# design.net
KiCad netlist of a schematic drawn in Altium Designer
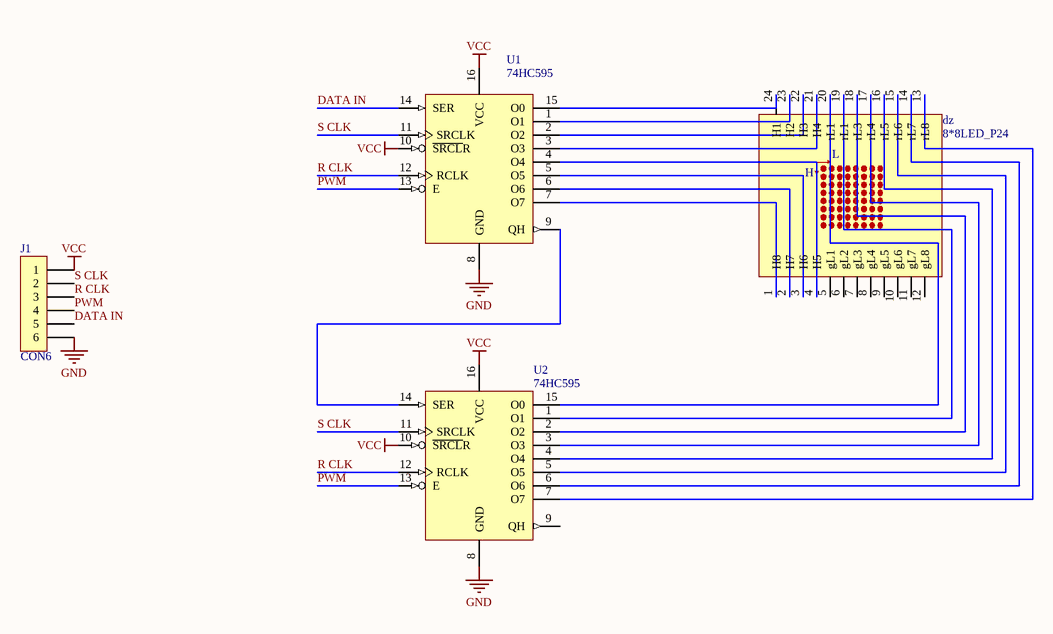
[diagram p0: 点阵.SchDoc]

(export (version "E")
  (design (tool "Eeschema 10.0.6"))
  (components
    (comp (ref "dz") (value "8*8LED_P24") (footprint "双色点阵") (libsource (lib "LED数码管") (part "8*8LED_P24")))
    (comp (ref "J1")
      (value "CON6")
      (footprint "sip-6")
      (description "Connector")
      (libsource (lib "接口") (part "CON6"))
    )
    (comp (ref "U1") (value "74HC595") (footprint "DIP-16") (libsource (lib "74xxTTL") (part "74HC595")))
    (comp (ref "U2") (value "74HC595") (footprint "DIP-16") (libsource (lib "74xxTTL") (part "74HC595")))
  )
  (nets
    (net (code "1") (name "/DATA IN") (class "Default")
      (node (ref "J1") (pin "5") (pinfunction "5_5") (pintype "passive"))
      (node (ref "U1") (pin "14") (pinfunction "SER_14") (pintype "input"))
    )
    (net (code "2") (name "/PWM") (class "Default")
      (node (ref "J1") (pin "4") (pinfunction "4_4") (pintype "passive"))
      (node (ref "U1") (pin "13") (pinfunction "E_13") (pintype "input"))
      (node (ref "U2") (pin "13") (pinfunction "E_13") (pintype "input"))
    )
    (net (code "3") (name "/R CLK") (class "Default")
      (node (ref "J1") (pin "3") (pinfunction "3_3") (pintype "passive"))
      (node (ref "U1") (pin "12") (pinfunction "RCLK_12") (pintype "input"))
      (node (ref "U2") (pin "12") (pinfunction "RCLK_12") (pintype "input"))
    )
    (net (code "4") (name "/S CLK") (class "Default")
      (node (ref "J1") (pin "2") (pinfunction "2_2") (pintype "passive"))
      (node (ref "U1") (pin "11") (pinfunction "SRCLK_11") (pintype "input"))
      (node (ref "U2") (pin "11") (pinfunction "SRCLK_11") (pintype "input"))
    )
    (net (code "5") (name "GND") (class "Default")
      (node (ref "J1") (pin "6") (pinfunction "6_6") (pintype "passive"))
      (node (ref "U1") (pin "8") (pinfunction "GND_8") (pintype "power_in"))
      (node (ref "U2") (pin "8") (pinfunction "GND_8") (pintype "power_in"))
    )
    (net (code "6") (name "Net-(U1-O0)") (class "Default")
      (node (ref "U1") (pin "15") (pinfunction "O0_15") (pintype "tri_state"))
      (node (ref "dz") (pin "24") (pinfunction "H1_24") (pintype "passive"))
    )
    (net (code "7") (name "Net-(U1-O1)") (class "Default")
      (node (ref "U1") (pin "1") (pinfunction "O1_1") (pintype "tri_state"))
      (node (ref "dz") (pin "23") (pinfunction "H2_23") (pintype "passive"))
    )
    (net (code "8") (name "Net-(U1-O2)") (class "Default")
      (node (ref "U1") (pin "2") (pinfunction "O2_2") (pintype "tri_state"))
      (node (ref "dz") (pin "22") (pinfunction "H3_22") (pintype "passive"))
    )
    (net (code "9") (name "Net-(U1-O3)") (class "Default")
      (node (ref "U1") (pin "3") (pinfunction "O3_3") (pintype "tri_state"))
      (node (ref "dz") (pin "21") (pinfunction "H4_21") (pintype "passive"))
    )
    (net (code "10") (name "Net-(U1-O4)") (class "Default")
      (node (ref "U1") (pin "4") (pinfunction "O4_4") (pintype "tri_state"))
      (node (ref "dz") (pin "4") (pinfunction "H5_4") (pintype "passive"))
    )
    (net (code "11") (name "Net-(U1-O5)") (class "Default")
      (node (ref "U1") (pin "5") (pinfunction "O5_5") (pintype "tri_state"))
      (node (ref "dz") (pin "3") (pinfunction "H6_3") (pintype "passive"))
    )
    (net (code "12") (name "Net-(U1-O6)") (class "Default")
      (node (ref "U1") (pin "6") (pinfunction "O6_6") (pintype "tri_state"))
      (node (ref "dz") (pin "2") (pinfunction "H7_2") (pintype "passive"))
    )
    (net (code "13") (name "Net-(U1-O7)") (class "Default")
      (node (ref "U1") (pin "7") (pinfunction "O7_7") (pintype "tri_state"))
      (node (ref "dz") (pin "1") (pinfunction "H8_1") (pintype "passive"))
    )
    (net (code "14") (name "Net-(U1-QH)") (class "Default")
      (node (ref "U1") (pin "9") (pinfunction "QH_9") (pintype "output"))
      (node (ref "U2") (pin "14") (pinfunction "SER_14") (pintype "input"))
    )
    (net (code "15") (name "Net-(U2-O0)") (class "Default")
      (node (ref "U2") (pin "15") (pinfunction "O0_15") (pintype "tri_state"))
      (node (ref "dz") (pin "20") (pinfunction "rL1_20") (pintype "passive"))
    )
    (net (code "16") (name "Net-(U2-O1)") (class "Default")
      (node (ref "U2") (pin "1") (pinfunction "O1_1") (pintype "tri_state"))
      (node (ref "dz") (pin "19") (pinfunction "rL1_19") (pintype "passive"))
    )
    (net (code "17") (name "Net-(U2-O2)") (class "Default")
      (node (ref "U2") (pin "2") (pinfunction "O2_2") (pintype "tri_state"))
      (node (ref "dz") (pin "18") (pinfunction "rL3_18") (pintype "passive"))
    )
    (net (code "18") (name "Net-(U2-O3)") (class "Default")
      (node (ref "U2") (pin "3") (pinfunction "O3_3") (pintype "tri_state"))
      (node (ref "dz") (pin "17") (pinfunction "rL4_17") (pintype "passive"))
    )
    (net (code "19") (name "Net-(U2-O4)") (class "Default")
      (node (ref "U2") (pin "4") (pinfunction "O4_4") (pintype "tri_state"))
      (node (ref "dz") (pin "16") (pinfunction "rL5_16") (pintype "passive"))
    )
    (net (code "20") (name "Net-(U2-O5)") (class "Default")
      (node (ref "U2") (pin "5") (pinfunction "O5_5") (pintype "tri_state"))
      (node (ref "dz") (pin "15") (pinfunction "rL6_15") (pintype "passive"))
    )
    (net (code "21") (name "Net-(U2-O6)") (class "Default")
      (node (ref "U2") (pin "6") (pinfunction "O6_6") (pintype "tri_state"))
      (node (ref "dz") (pin "14") (pinfunction "rL7_14") (pintype "passive"))
    )
    (net (code "22") (name "Net-(U2-O7)") (class "Default")
      (node (ref "U2") (pin "7") (pinfunction "O7_7") (pintype "tri_state"))
      (node (ref "dz") (pin "13") (pinfunction "rL8_13") (pintype "passive"))
    )
    (net (code "23") (name "VCC") (class "Default")
      (node (ref "J1") (pin "1") (pinfunction "1_1") (pintype "passive"))
      (node (ref "U1") (pin "10") (pinfunction "~{SRCL}R_10") (pintype "input"))
      (node (ref "U1") (pin "16") (pinfunction "VCC_16") (pintype "power_in"))
      (node (ref "U2") (pin "10") (pinfunction "~{SRCL}R_10") (pintype "input"))
      (node (ref "U2") (pin "16") (pinfunction "VCC_16") (pintype "power_in"))
    )
    (net (code "24") (name "unconnected-(U2-QH-Pad9)") (class "Default")
      (node (ref "U2") (pin "9") (pinfunction "QH_9") (pintype "output"))
    )
    (net (code "25") (name "unconnected-(dz-gL1-Pad5)") (class "Default")
      (node (ref "dz") (pin "5") (pinfunction "gL1_5") (pintype "passive"))
    )
    (net (code "26") (name "unconnected-(dz-gL2-Pad6)") (class "Default")
      (node (ref "dz") (pin "6") (pinfunction "gL2_6") (pintype "passive"))
    )
    (net (code "27") (name "unconnected-(dz-gL3-Pad7)") (class "Default")
      (node (ref "dz") (pin "7") (pinfunction "gL3_7") (pintype "passive"))
    )
    (net (code "28") (name "unconnected-(dz-gL4-Pad8)") (class "Default")
      (node (ref "dz") (pin "8") (pinfunction "gL4_8") (pintype "passive"))
    )
    (net (code "29") (name "unconnected-(dz-gL5-Pad9)") (class "Default")
      (node (ref "dz") (pin "9") (pinfunction "gL5_9") (pintype "passive"))
    )
    (net (code "30") (name "unconnected-(dz-gL6-Pad10)") (class "Default")
      (node (ref "dz") (pin "10") (pinfunction "gL6_10") (pintype "passive"))
    )
    (net (code "31") (name "unconnected-(dz-gL7-Pad11)") (class "Default")
      (node (ref "dz") (pin "11") (pinfunction "gL7_11") (pintype "passive"))
    )
    (net (code "32") (name "unconnected-(dz-gL8-Pad12)") (class "Default")
      (node (ref "dz") (pin "12") (pinfunction "gL8_12") (pintype "passive"))
    )
  )
)
